# FULL_CB_Power_REV_D.net
KiCad netlist of a schematic drawn in Altium Designer
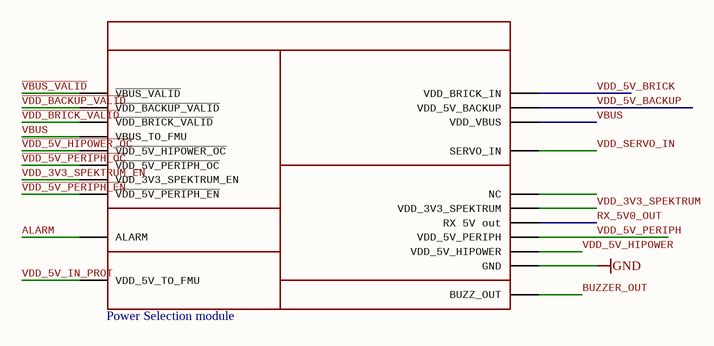
[diagram p0: FULL_CB_Power_REV_D.SchDoc]

(export (version "E")
  (design (tool "Eeschema 10.0.6"))
  (components
    (comp (ref "PSM200")
      (value "Power Selection module")
      (footprint "PSM")
      (description "PCA, PSM, Assembly")
      (libsource (lib "CB_REV_C") (part "PSMPSM"))
    )
  )
  (nets
    (net (code "1") (name "/ALARM") (class "Default")
      (node (ref "PSM200") (pin "ALARM") (pinfunction "ALARM_ALARM") (pintype "passive"))
    )
    (net (code "2") (name "/BUZZER_OUT") (class "Default")
      (node (ref "PSM200") (pin "BUZZER_OUT") (pinfunction "BUZZ_OUT_BUZZER_OUT") (pintype "passive"))
    )
    (net (code "3") (name "/RX_5V0_OUT") (class "Default")
      (node (ref "PSM200") (pin "RX") (pinfunction "RX_5V_out_RX") (pintype "passive"))
    )
    (net (code "4") (name "/VBUS") (class "Default")
      (node (ref "PSM200") (pin "VBUS") (pinfunction "VBUS_TO_FMU_VBUS") (pintype "passive"))
      (node (ref "PSM200") (pin "VDD_VBUS") (pinfunction "VDD_VBUS_VDD_VBUS") (pintype "passive"))
    )
    (net (code "5") (name "/VDD_3V3_SPEKTRUM") (class "Default")
      (node (ref "PSM200") (pin "SPEK") (pinfunction "VDD_3V3_SPEKTRUM_SPEK") (pintype "passive"))
    )
    (net (code "6") (name "/VDD_3V3_SPEKTRUM_EN") (class "Default")
      (node (ref "PSM200") (pin "VDD_3V3_SPEKTRUM_EN") (pinfunction "VDD_3V3_SPEKTRUM_EN_VDD_3V3_SPEKTRUM_EN") (pintype "passive"))
    )
    (net (code "7") (name "/VDD_5V_BACKUP") (class "Default")
      (node (ref "PSM200") (pin "VDD_5V_BACKUP") (pinfunction "VDD_5V_BACKUP_VDD_5V_BACKUP") (pintype "passive"))
    )
    (net (code "8") (name "/VDD_5V_BRICK") (class "Default")
      (node (ref "PSM200") (pin "VDD_BRICK_IN") (pinfunction "VDD_BRICK_IN_VDD_BRICK_IN") (pintype "passive"))
    )
    (net (code "9") (name "/VDD_5V_HIPOWER") (class "Default")
      (node (ref "PSM200") (pin "5V_HIPOWER") (pinfunction "VDD_5V_HIPOWER_5V_HIPOWER") (pintype "passive"))
    )
    (net (code "10") (name "/VDD_5V_IN_PROT") (class "Default")
      (node (ref "PSM200") (pin "VDD_5V_IN_PROT") (pinfunction "VDD_5V_TO_FMU_VDD_5V_IN_PROT") (pintype "passive"))
    )
    (net (code "11") (name "/VDD_5V_PERIPH") (class "Default")
      (node (ref "PSM200") (pin "5V_PERIPH") (pinfunction "VDD_5V_PERIPH_5V_PERIPH") (pintype "passive"))
    )
    (net (code "12") (name "/VDD_SERVO_IN") (class "Default")
      (node (ref "PSM200") (pin "SERVO_IN") (pinfunction "SERVO_IN_SERVO_IN") (pintype "passive"))
    )
    (net (code "13") (name "/~{VBUS_VALID}") (class "Default")
      (node (ref "PSM200") (pin "!VBUS_VALID") (pinfunction "~{VBUS_VALID}_!VBUS_VALID") (pintype "passive"))
    )
    (net (code "14") (name "/~{VDD_5V_HIPOWER_OC}") (class "Default")
      (node (ref "PSM200") (pin "!VDD_5V_HIPOWER_OC") (pinfunction "~{VDD_5V_HIPOWER_OC}_!VDD_5V_HIPOWER_OC") (pintype "passive"))
    )
    (net (code "15") (name "/~{VDD_5V_PERIPH_EN}") (class "Default")
      (node (ref "PSM200") (pin "!VDD_5V_PERIPH_EN") (pinfunction "~{VDD_5V_PERIPH_EN}_!VDD_5V_PERIPH_EN") (pintype "passive"))
    )
    (net (code "16") (name "/~{VDD_5V_PERIPH_OC}") (class "Default")
      (node (ref "PSM200") (pin "!VDD_5V_PERIPH_OC") (pinfunction "~{VDD_5V_PERIPH_OC}_!VDD_5V_PERIPH_OC") (pintype "passive"))
    )
    (net (code "17") (name "/~{VDD_BACKUP_VALID}") (class "Default")
      (node (ref "PSM200") (pin "!VDD_BACKUP_VALID") (pinfunction "~{VDD_BACKUP_VALID}_!VDD_BACKUP_VALID") (pintype "passive"))
    )
    (net (code "18") (name "/~{VDD_BRICK_VALID}") (class "Default")
      (node (ref "PSM200") (pin "!VDD_BRICK_VALID") (pinfunction "~{VDD_BRICK_VALID}_!VDD_BRICK_VALID") (pintype "passive"))
    )
    (net (code "19") (name "GND") (class "Default")
      (node (ref "PSM200") (pin "GND") (pinfunction "GND_GND") (pintype "passive"))
    )
    (net (code "20") (name "unconnected-(PSM200-PadNC)") (class "Default")
      (node (ref "PSM200") (pin "NC") (pinfunction "NC_NC") (pintype "passive"))
    )
  )
)
